# SPECTROMETER.net
KiCad netlist of a schematic drawn in EAGLE
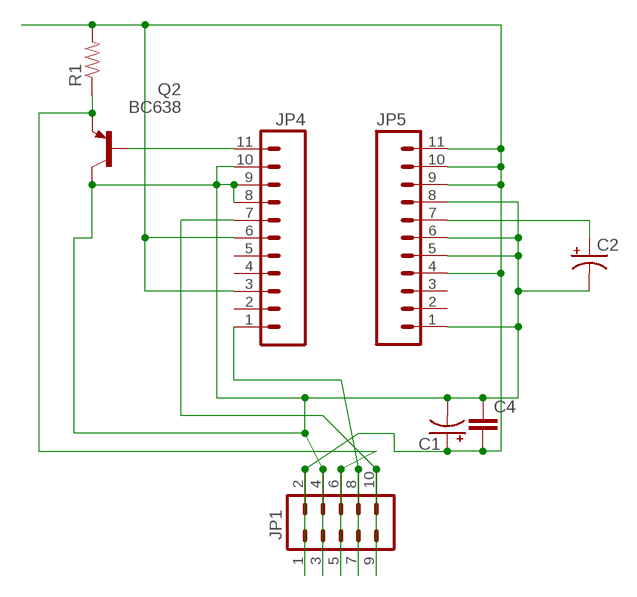
[diagram p0: schematic, sheet 1]

(export (version "E")
  (design (tool "Eeschema 10.0.6"))
  (components
    (comp (ref "C1")
      (value "CAP_POLPTH1")
      (footprint "eagle-import:CPOL-RADIAL-100UF-25V")
      (libsource (lib "eagle-import") (part "CAP_POLPTH1"))
    )
    (comp (ref "C2")
      (value "CAP_POLPTH1")
      (footprint "eagle-import:CPOL-RADIAL-100UF-25V")
      (libsource (lib "eagle-import") (part "CAP_POLPTH1"))
    )
    (comp (ref "C4")
      (value "CAPPTH1")
      (footprint "eagle-import:CAP-PTH-5MM")
      (libsource (lib "eagle-import") (part "CAPPTH1"))
    )
    (comp (ref "JP1")
      (value "M05X2NO_SILK")
      (footprint "eagle-import:2X5_NOSILK")
      (libsource (lib "eagle-import") (part "M05X2NO_SILK"))
    )
    (comp (ref "JP4")
      (value "M11LOCK")
      (footprint "eagle-import:1X11_LOCK")
      (libsource (lib "eagle-import") (part "M11LOCK"))
    )
    (comp (ref "JP5")
      (value "M11LOCK")
      (footprint "eagle-import:1X11_LOCK")
      (libsource (lib "eagle-import") (part "M11LOCK"))
    )
    (comp (ref "Q2")
      (value "BC638")
      (footprint "eagle-import:TO92-BCE")
      (libsource (lib "eagle-import") (part "BC638"))
    )
    (comp (ref "R1")
      (value "RESISTORKIT")
      (footprint "eagle-import:AXIAL-0.3-KIT")
      (libsource (lib "eagle-import") (part "RESISTORKIT"))
    )
  )
  (nets
    (net (code "1") (name "Net-(C1-+)") (class "Default")
      (node (ref "C1") (pin "1") (pinfunction "+_1") (pintype "passive"))
      (node (ref "C4") (pin "2") (pinfunction "2_2") (pintype "passive"))
      (node (ref "JP1") (pin "1") (pinfunction "1_1") (pintype "passive"))
      (node (ref "JP1") (pin "2") (pinfunction "2_2") (pintype "passive"))
      (node (ref "JP4") (pin "3") (pinfunction "3_3") (pintype "passive"))
      (node (ref "JP4") (pin "6") (pinfunction "6_6") (pintype "passive"))
      (node (ref "JP5") (pin "10") (pinfunction "10_10") (pintype "passive"))
      (node (ref "JP5") (pin "11") (pinfunction "11_11") (pintype "passive"))
      (node (ref "JP5") (pin "4") (pinfunction "4_4") (pintype "passive"))
      (node (ref "JP5") (pin "9") (pinfunction "9_9") (pintype "passive"))
      (node (ref "R1") (pin "P$2") (pinfunction "2_P$2") (pintype "passive"))
    )
    (net (code "2") (name "Net-(C1--)") (class "Default")
      (node (ref "C1") (pin "2") (pinfunction "-_2") (pintype "passive"))
      (node (ref "C2") (pin "2") (pinfunction "-_2") (pintype "passive"))
      (node (ref "C4") (pin "1") (pinfunction "1_1") (pintype "passive"))
      (node (ref "JP1") (pin "3") (pinfunction "3_3") (pintype "passive"))
      (node (ref "JP1") (pin "4") (pinfunction "4_4") (pintype "passive"))
      (node (ref "JP4") (pin "10") (pinfunction "10_10") (pintype "passive"))
      (node (ref "JP4") (pin "8") (pinfunction "8_8") (pintype "passive"))
      (node (ref "JP4") (pin "9") (pinfunction "9_9") (pintype "passive"))
      (node (ref "JP5") (pin "1") (pinfunction "1_1") (pintype "passive"))
      (node (ref "JP5") (pin "5") (pinfunction "5_5") (pintype "passive"))
      (node (ref "JP5") (pin "6") (pinfunction "6_6") (pintype "passive"))
      (node (ref "JP5") (pin "8") (pinfunction "8_8") (pintype "passive"))
      (node (ref "Q2") (pin "C") (pinfunction "C_C") (pintype "passive"))
    )
    (net (code "3") (name "Net-(C2-+)") (class "Default")
      (node (ref "C2") (pin "1") (pinfunction "+_1") (pintype "passive"))
      (node (ref "JP5") (pin "7") (pinfunction "7_7") (pintype "passive"))
    )
    (net (code "4") (name "Net-(JP1-Pad7)") (class "Default")
      (node (ref "JP1") (pin "7") (pinfunction "7_7") (pintype "passive"))
      (node (ref "JP1") (pin "8") (pinfunction "8_8") (pintype "passive"))
      (node (ref "JP4") (pin "1") (pinfunction "1_1") (pintype "passive"))
    )
    (net (code "5") (name "Net-(JP1-Pad10)") (class "Default")
      (node (ref "JP1") (pin "10") (pinfunction "10_10") (pintype "passive"))
      (node (ref "JP1") (pin "9") (pinfunction "9_9") (pintype "passive"))
      (node (ref "JP4") (pin "7") (pinfunction "7_7") (pintype "passive"))
    )
    (net (code "6") (name "Net-(JP4-Pad11)") (class "Default")
      (node (ref "JP4") (pin "11") (pinfunction "11_11") (pintype "passive"))
      (node (ref "Q2") (pin "B") (pinfunction "B_B") (pintype "passive"))
    )
    (net (code "7") (name "Net-(R1-1)") (class "Default")
      (node (ref "JP1") (pin "5") (pinfunction "5_5") (pintype "passive"))
      (node (ref "JP1") (pin "6") (pinfunction "6_6") (pintype "passive"))
      (node (ref "Q2") (pin "E") (pinfunction "E_E") (pintype "passive"))
      (node (ref "R1") (pin "P$1") (pinfunction "1_P$1") (pintype "passive"))
    )
    (net (code "8") (name "unconnected-(JP4-Pad2)") (class "Default")
      (node (ref "JP4") (pin "2") (pinfunction "2_2") (pintype "passive"))
    )
    (net (code "9") (name "unconnected-(JP4-Pad4)") (class "Default")
      (node (ref "JP4") (pin "4") (pinfunction "4_4") (pintype "passive"))
    )
    (net (code "10") (name "unconnected-(JP4-Pad5)") (class "Default")
      (node (ref "JP4") (pin "5") (pinfunction "5_5") (pintype "passive"))
    )
    (net (code "11") (name "unconnected-(JP5-Pad2)") (class "Default")
      (node (ref "JP5") (pin "2") (pinfunction "2_2") (pintype "passive"))
    )
    (net (code "12") (name "unconnected-(JP5-Pad3)") (class "Default")
      (node (ref "JP5") (pin "3") (pinfunction "3_3") (pintype "passive"))
    )
  )
)
